# esp32-s3_connect_lcd.net
KiCad netlist of a schematic drawn in Altium Designer
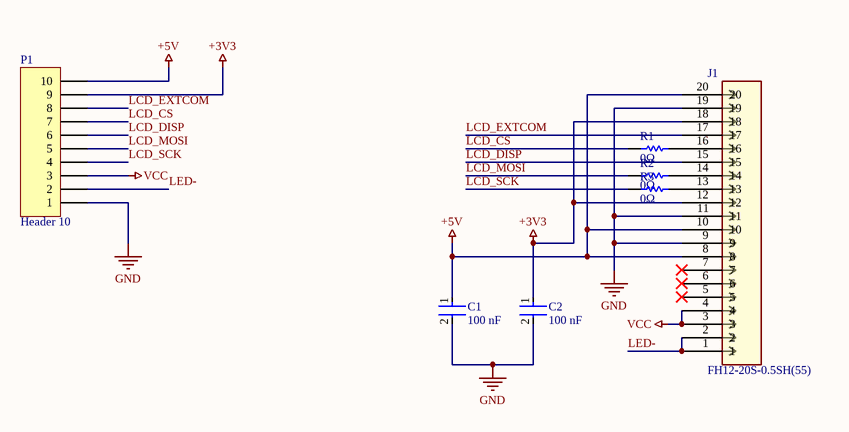
[diagram p0: esp32-s3_connect_lcd.SchDoc]

(export (version "E")
  (design (tool "Eeschema 10.0.6"))
  (components
    (comp (ref "C1")
      (value "100 nF")
      (footprint "FP-CC0603-DA-MFG")
      (description "50V 100nF X7R ±10% 0603 Multilayer Ceramic Capacitors MLCC - SMD/SMT ROHS")
      (fields (field (name "MANUFACTURER") "YAGEO") (field (name "MFR. PART #") "CC0603KRX7R9BB104"))
      (libsource (lib "Altium Content Vault") (part "11868f565c42a9108669ba33697ecf6"))
    )
    (comp (ref "C2")
      (value "100 nF")
      (footprint "FP-CC0603-DA-MFG")
      (description "50V 100nF X7R ±10% 0603 Multilayer Ceramic Capacitors MLCC - SMD/SMT ROHS")
      (fields (field (name "MANUFACTURER") "YAGEO") (field (name "MFR. PART #") "CC0603KRX7R9BB104"))
      (libsource (lib "Altium Content Vault") (part "11868f565c42a9108669ba33697ecf6"))
    )
    (comp (ref "J1")
      (value "FH12-20S-0.5SH(55)")
      (footprint "CONN20_FH12-20S_HIR")
      (fields (field (name "MANUFACTURER") "HRS(Hirose)") (field (name "LCSC PART #") "C596730"))
      (libsource (lib "FH12-20S-0P5SH55") (part "FH12-20S-0.5SH55"))
    )
    (comp (ref "P1")
      (value "Header 10")
      (footprint "HDR1X10")
      (description "Header, 10-Pin")
      (fields (field (name "PUBLISHER") "Altium Limited"))
      (libsource (lib "Miscellaneous Connectors") (part "Header 10"))
    )
    (comp (ref "R1")
      (value "0Ω")
      (footprint "RESC2013X50X30LL20T20")
      (description "125mW Thick Film Resistors 200V 0Ω 0805 Chip Resistor - Surface Mount ROHS")
      (fields
        (field (name "MFR. PART #") "CRCW08050000Z0EA")
        (field (name "MANUFACTURER") "Vishay Intertech")
      )
      (libsource (lib "Altium Content Vault") (part "RES"))
    )
    (comp (ref "R2")
      (value "0Ω")
      (footprint "RESC2013X50X30LL20T20")
      (description "125mW Thick Film Resistors 200V 0Ω 0805 Chip Resistor - Surface Mount ROHS")
      (fields
        (field (name "MFR. PART #") "CRCW08050000Z0EA")
        (field (name "MANUFACTURER") "Vishay Intertech")
      )
      (libsource (lib "Altium Content Vault") (part "RES"))
    )
    (comp (ref "R3")
      (value "0Ω")
      (footprint "RESC2013X50X30LL20T20")
      (description "125mW Thick Film Resistors 200V 0Ω 0805 Chip Resistor - Surface Mount ROHS")
      (fields
        (field (name "MFR. PART #") "CRCW08050000Z0EA")
        (field (name "MANUFACTURER") "Vishay Intertech")
      )
      (libsource (lib "Altium Content Vault") (part "RES"))
    )
  )
  (nets
    (net (code "1") (name "+3V3") (class "Default")
      (node (ref "C2") (pin "1") (pinfunction "1_1") (pintype "passive"))
      (node (ref "J1") (pin "12") (pinfunction "12_12") (pintype "passive"))
      (node (ref "J1") (pin "18") (pinfunction "18_18") (pintype "passive"))
      (node (ref "P1") (pin "9") (pinfunction "9_9") (pintype "passive"))
    )
    (net (code "2") (name "+5V") (class "Default")
      (node (ref "C1") (pin "1") (pinfunction "1_1") (pintype "passive"))
      (node (ref "J1") (pin "10") (pinfunction "10_10") (pintype "passive"))
      (node (ref "J1") (pin "20") (pinfunction "20_20") (pintype "passive"))
      (node (ref "J1") (pin "8") (pinfunction "8_8") (pintype "passive"))
      (node (ref "P1") (pin "10") (pinfunction "10_10") (pintype "passive"))
    )
    (net (code "3") (name "/LCD_CS") (class "Default")
      (node (ref "P1") (pin "7") (pinfunction "7_7") (pintype "passive"))
      (node (ref "R1") (pin "1") (pinfunction "1_1") (pintype "passive"))
    )
    (net (code "4") (name "/LCD_DISP") (class "Default")
      (node (ref "J1") (pin "15") (pinfunction "15_15") (pintype "passive"))
      (node (ref "P1") (pin "6") (pinfunction "6_6") (pintype "passive"))
    )
    (net (code "5") (name "/LCD_EXTCOM") (class "Default")
      (node (ref "J1") (pin "17") (pinfunction "17_17") (pintype "passive"))
      (node (ref "P1") (pin "8") (pinfunction "8_8") (pintype "passive"))
    )
    (net (code "6") (name "/LCD_MOSI") (class "Default")
      (node (ref "P1") (pin "5") (pinfunction "5_5") (pintype "passive"))
      (node (ref "R2") (pin "1") (pinfunction "1_1") (pintype "passive"))
    )
    (net (code "7") (name "/LCD_SCK") (class "Default")
      (node (ref "P1") (pin "4") (pinfunction "4_4") (pintype "passive"))
      (node (ref "R3") (pin "1") (pinfunction "1_1") (pintype "passive"))
    )
    (net (code "8") (name "/LED-") (class "Default")
      (node (ref "J1") (pin "1") (pinfunction "1_1") (pintype "passive"))
      (node (ref "J1") (pin "2") (pinfunction "2_2") (pintype "passive"))
      (node (ref "P1") (pin "2") (pinfunction "2_2") (pintype "passive"))
    )
    (net (code "9") (name "GND") (class "Default")
      (node (ref "C1") (pin "2") (pinfunction "2_2") (pintype "passive"))
      (node (ref "C2") (pin "2") (pinfunction "2_2") (pintype "passive"))
      (node (ref "J1") (pin "11") (pinfunction "11_11") (pintype "passive"))
      (node (ref "J1") (pin "19") (pinfunction "19_19") (pintype "passive"))
      (node (ref "J1") (pin "9") (pinfunction "9_9") (pintype "passive"))
      (node (ref "P1") (pin "1") (pinfunction "1_1") (pintype "passive"))
    )
    (net (code "10") (name "Net-(J1-Pad13)") (class "Default")
      (node (ref "J1") (pin "13") (pinfunction "13_13") (pintype "passive"))
      (node (ref "R3") (pin "2") (pinfunction "2_2") (pintype "passive"))
    )
    (net (code "11") (name "Net-(J1-Pad14)") (class "Default")
      (node (ref "J1") (pin "14") (pinfunction "14_14") (pintype "passive"))
      (node (ref "R2") (pin "2") (pinfunction "2_2") (pintype "passive"))
    )
    (net (code "12") (name "Net-(J1-Pad16)") (class "Default")
      (node (ref "J1") (pin "16") (pinfunction "16_16") (pintype "passive"))
      (node (ref "R1") (pin "2") (pinfunction "2_2") (pintype "passive"))
    )
    (net (code "13") (name "VCC") (class "Default")
      (node (ref "J1") (pin "3") (pinfunction "3_3") (pintype "passive"))
      (node (ref "J1") (pin "4") (pinfunction "4_4") (pintype "passive"))
      (node (ref "P1") (pin "3") (pinfunction "3_3") (pintype "passive"))
    )
    (net (code "14") (name "unconnected-(J1-Pad5)") (class "Default")
      (node (ref "J1") (pin "5") (pinfunction "5_5") (pintype "passive+no_connect"))
    )
    (net (code "15") (name "unconnected-(J1-Pad6)") (class "Default")
      (node (ref "J1") (pin "6") (pinfunction "6_6") (pintype "passive+no_connect"))
    )
    (net (code "16") (name "unconnected-(J1-Pad7)") (class "Default")
      (node (ref "J1") (pin "7") (pinfunction "7_7") (pintype "passive+no_connect"))
    )
  )
)
